# Sheet1.net
KiCad netlist of a schematic drawn in Altium Designer
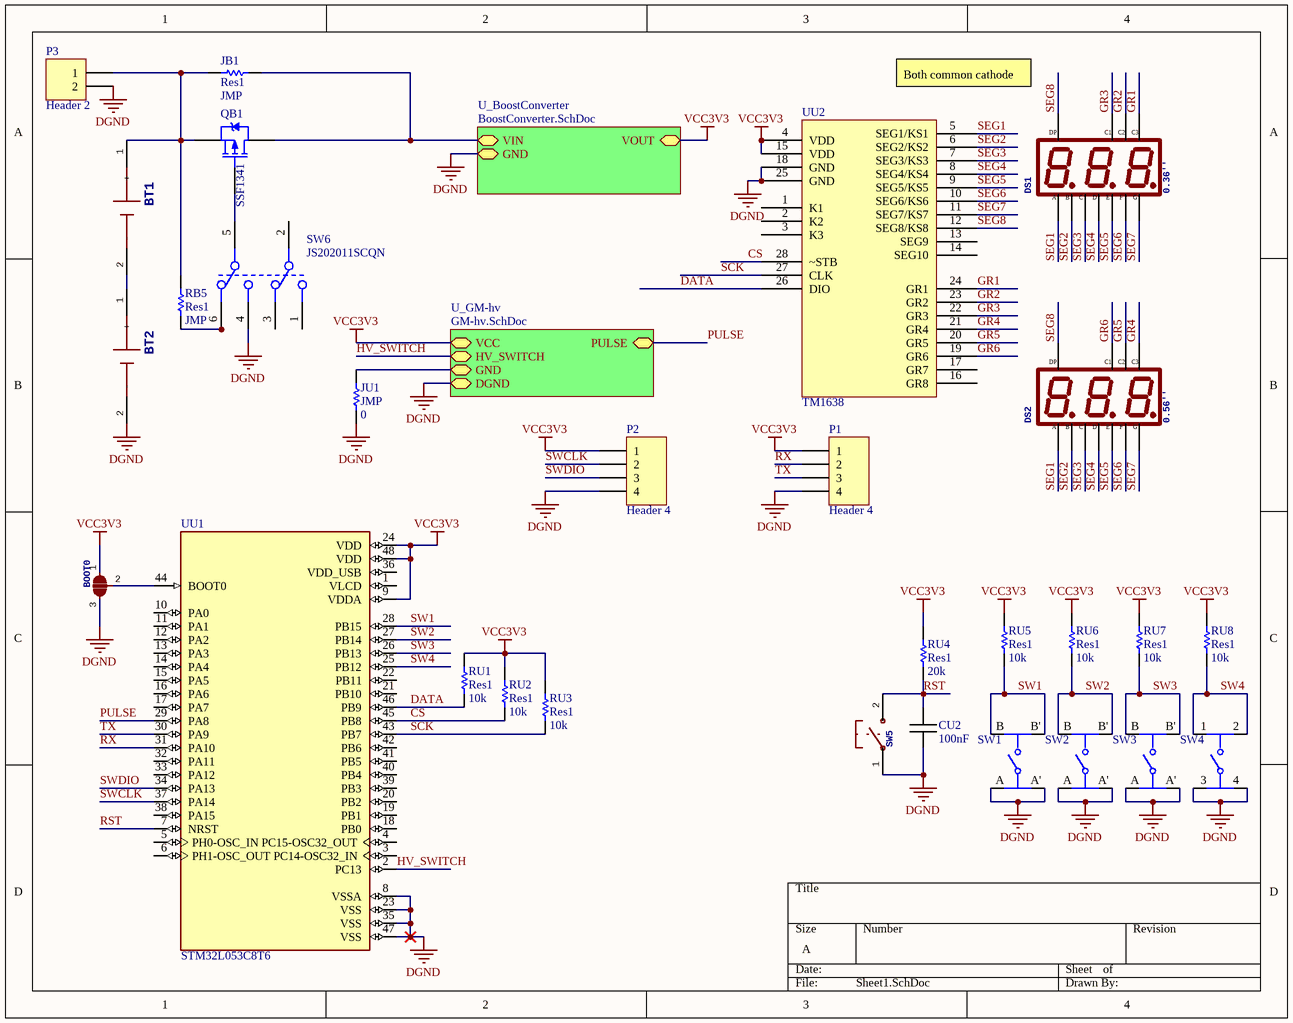
[diagram p0: Sheet1.SchDoc]

(export (version "E")
  (design (tool "Eeschema 10.0.6"))
  (components
    (comp (ref "BOOT0")
      (value "2-Way Solder Jumper")
      (footprint "SOLDERJUMPER_2WAY_OPEN_NOPASTE")
      (libsource (lib "Standard2") (part "SOLDERJUMPER_2WAY0603"))
    )
    (comp (ref "BT1")
      (value "Holder Cr2032 Gold Leads Smd")
      (footprint "AAA holder smd")
      (fields (field (name "MF") "MPD") (field (name "MP") "BU2032SM-BT-GTR"))
      (libsource (lib "Battery Holders") (part "BU2032SM-BT-GTR"))
    )
    (comp (ref "BT2")
      (value "Holder Cr2032 Gold Leads Smd")
      (footprint "AAA holder smd")
      (fields (field (name "MF") "MPD") (field (name "MP") "BU2032SM-BT-GTR"))
      (libsource (lib "Battery Holders") (part "BU2032SM-BT-GTR"))
    )
    (comp (ref "CU2") (value "100nF") (footprint "CAP0603R") (libsource (lib "Standard") (part "Capacitor")))
    (comp (ref "DS1")
      (value "0.36''")
      (footprint "7-seg 3bit 0.36")
      (fields (field (name "MP") "BA56-12EWA") (field (name "MF") "Kingbright"))
      (libsource (lib "LEDs") (part "BA56-12EWA"))
    )
    (comp (ref "DS2")
      (value "0.56''")
      (footprint "BA56-12EWA")
      (fields (field (name "MP") "BA56-12EWA") (field (name "MF") "Kingbright"))
      (libsource (lib "LEDs") (part "BA56-12EWA"))
    )
    (comp (ref "JB1")
      (value "Res1")
      (footprint "RES0603R")
      (description "Resistor")
      (fields (field (name "ALTIUM_VALUE") "JMP") (field (name "PUBLISHER") "Altium Limited"))
      (libsource (lib "Miscellaneous Devices") (part "Res1"))
    )
    (comp (ref "JU1")
      (value "JMP")
      (footprint "RES0603R")
      (description "Resistor")
      (fields (field (name "ALTIUM_VALUE") "0") (field (name "PUBLISHER") "Altium Limited"))
      (libsource (lib "Miscellaneous Devices") (part "Res1"))
    )
    (comp (ref "P1")
      (value "Header 4")
      (footprint "HDR1X4")
      (description "Header, 4-Pin")
      (fields (field (name "PUBLISHER") "Altium Limited"))
      (libsource (lib "Miscellaneous Connectors") (part "Header 4"))
    )
    (comp (ref "P2")
      (value "Header 4")
      (footprint "HDR1X4")
      (description "Header, 4-Pin")
      (fields (field (name "PUBLISHER") "Altium Limited"))
      (libsource (lib "Miscellaneous Connectors") (part "Header 4"))
    )
    (comp (ref "P3")
      (value "Header 2")
      (footprint "HDR1X2")
      (description "Header, 2-Pin")
      (fields (field (name "PUBLISHER") "Altium Limited"))
      (libsource (lib "Miscellaneous Connectors") (part "Header 2"))
    )
    (comp (ref "QB1")
      (value "SSF1341")
      (footprint "SOT23")
      (description "P-Channel Power MOSFET PMV65XP")
      (fields (field (name "PART NUMBER") "1758119"))
      (libsource (lib "Standard") (part "PMOS"))
    )
    (comp (ref "RB5")
      (value "Res1")
      (footprint "RES0603R")
      (description "Resistor")
      (fields (field (name "ALTIUM_VALUE") "JMP") (field (name "PUBLISHER") "Altium Limited"))
      (libsource (lib "Miscellaneous Devices") (part "Res1"))
    )
    (comp (ref "RU1")
      (value "Res1")
      (footprint "RES0603R")
      (description "Resistor")
      (fields (field (name "ALTIUM_VALUE") "10k") (field (name "PUBLISHER") "Altium Limited"))
      (libsource (lib "Miscellaneous Devices") (part "Res1"))
    )
    (comp (ref "RU2")
      (value "Res1")
      (footprint "RES0603R")
      (description "Resistor")
      (fields (field (name "ALTIUM_VALUE") "10k") (field (name "PUBLISHER") "Altium Limited"))
      (libsource (lib "Miscellaneous Devices") (part "Res1"))
    )
    (comp (ref "RU3")
      (value "Res1")
      (footprint "RES0603R")
      (description "Resistor")
      (fields (field (name "ALTIUM_VALUE") "10k") (field (name "PUBLISHER") "Altium Limited"))
      (libsource (lib "Miscellaneous Devices") (part "Res1"))
    )
    (comp (ref "RU4")
      (value "Res1")
      (footprint "RES0603R")
      (description "Resistor")
      (fields (field (name "ALTIUM_VALUE") "20k") (field (name "PUBLISHER") "Altium Limited"))
      (libsource (lib "Miscellaneous Devices") (part "Res1"))
    )
    (comp (ref "RU5")
      (value "Res1")
      (footprint "RES0603R")
      (description "Resistor")
      (fields (field (name "ALTIUM_VALUE") "10k") (field (name "PUBLISHER") "Altium Limited"))
      (libsource (lib "Standard") (part "Res1"))
    )
    (comp (ref "RU6")
      (value "Res1")
      (footprint "RES0603R")
      (description "Resistor")
      (fields (field (name "ALTIUM_VALUE") "10k") (field (name "PUBLISHER") "Altium Limited"))
      (libsource (lib "Standard") (part "Res1"))
    )
    (comp (ref "RU7")
      (value "Res1")
      (footprint "RES0603R")
      (description "Resistor")
      (fields (field (name "ALTIUM_VALUE") "10k") (field (name "PUBLISHER") "Altium Limited"))
      (libsource (lib "Standard") (part "Res1"))
    )
    (comp (ref "RU8")
      (value "Res1")
      (footprint "RES0603R")
      (description "Resistor")
      (fields (field (name "ALTIUM_VALUE") "10k") (field (name "PUBLISHER") "Altium Limited"))
      (libsource (lib "Standard") (part "Res1"))
    )
    (comp (ref "SW1")
      (value "EVQ-PAE05R")
      (footprint "FP-EVQ-PAE05R-MFG")
      (description "SWITCH TACTILE SPST-NO 0.02A 15V")
      (libsource (lib "Altium Content Vault") (part "75038bc65b1af1a6bd057da08483287"))
    )
    (comp (ref "SW2")
      (value "EVQ-PAE05R")
      (footprint "FP-EVQ-PAE05R-MFG")
      (description "SWITCH TACTILE SPST-NO 0.02A 15V")
      (libsource (lib "Altium Content Vault") (part "75038bc65b1af1a6bd057da08483287"))
    )
    (comp (ref "SW3")
      (value "EVQ-PAE05R")
      (footprint "FP-EVQ-PAE05R-MFG")
      (description "SWITCH TACTILE SPST-NO 0.02A 15V")
      (libsource (lib "Altium Content Vault") (part "75038bc65b1af1a6bd057da08483287"))
    )
    (comp (ref "SW4")
      (value "FSM100")
      (footprint "FP-FSM100-MFG")
      (description "SWITCH TACTILE SPST-NO 0.05A 24V")
      (libsource (lib "Altium Content Vault") (part "1adf0dd01260c80cf25a44bfd6b99ba"))
    )
    (comp (ref "SW5")
      (value "Switch")
      (footprint "PUSH_SMD_3x4")
      (fields (field (name "MANUFACTURER") "Omron") (field (name "MPN") "B3U-1000P"))
      (libsource (lib "Switches") (part "B3U-1000P"))
    )
    (comp (ref "SW6")
      (value "JS202011SCQN")
      (footprint "JS202011SCQN")
      (description "SWITCH SLIDE DPDT 300MA 6V")
      (libsource (lib "Switches") (part "JS202011SCQN"))
    )
    (comp (ref "UU1")
      (value "STM32L053C8T6")
      (footprint "LQFP48_7X7MM_0.5MMPP")
      (description "ARMÂ® CortexÂ®-M0+ STM32L0 Microcontroller IC 32-Bit 32MHz 64KB _64K x 8_ FLASH 48-LQFP _7x7_")
      (fields (field (name "DIGI-KEY_PART_NUMBER") "497-14906-ND") (field (name "MF") "STMicroelectronics"))
      (libsource (lib "STM") (part "STM32L053C8T6"))
    )
    (comp (ref "UU2")
      (value "TM1638")
      (footprint "SOP-28")
      (description "7Seg and keyboard driver")
      (libsource (lib "IC") (part "TM1638"))
    )
  )
  (nets
    (net (code "1") (name "/CS") (class "Default")
      (node (ref "RU2") (pin "2") (pinfunction "2_2") (pintype "passive"))
      (node (ref "UU1") (pin "45") (pinfunction "PB8_45") (pintype "bidirectional"))
      (node (ref "UU2") (pin "28") (pinfunction "~STB_28") (pintype "passive"))
    )
    (net (code "2") (name "/DATA") (class "Default")
      (node (ref "RU1") (pin "1") (pinfunction "1_1") (pintype "passive"))
      (node (ref "UU1") (pin "46") (pinfunction "PB9_46") (pintype "bidirectional"))
      (node (ref "UU2") (pin "26") (pinfunction "DIO_26") (pintype "passive"))
    )
    (net (code "3") (name "/GND") (class "Default")
      (node (ref "JU1") (pin "2") (pinfunction "2_2") (pintype "passive"))
    )
    (net (code "4") (name "/GR1") (class "Default")
      (node (ref "DS1") (pin "12") (pinfunction "CA@3_12") (pintype "passive"))
      (node (ref "UU2") (pin "24") (pinfunction "GR1_24") (pintype "passive"))
    )
    (net (code "5") (name "/GR2") (class "Default")
      (node (ref "DS1") (pin "9") (pinfunction "CA@2_9") (pintype "passive"))
      (node (ref "UU2") (pin "23") (pinfunction "GR2_23") (pintype "passive"))
    )
    (net (code "6") (name "/GR3") (class "Default")
      (node (ref "DS1") (pin "8") (pinfunction "CA@1_8") (pintype "passive"))
      (node (ref "UU2") (pin "22") (pinfunction "GR3_22") (pintype "passive"))
    )
    (net (code "7") (name "/GR4") (class "Default")
      (node (ref "DS2") (pin "12") (pinfunction "CA@3_12") (pintype "passive"))
      (node (ref "UU2") (pin "21") (pinfunction "GR4_21") (pintype "passive"))
    )
    (net (code "8") (name "/GR5") (class "Default")
      (node (ref "DS2") (pin "9") (pinfunction "CA@2_9") (pintype "passive"))
      (node (ref "UU2") (pin "20") (pinfunction "GR5_20") (pintype "passive"))
    )
    (net (code "9") (name "/GR6") (class "Default")
      (node (ref "DS2") (pin "8") (pinfunction "CA@1_8") (pintype "passive"))
      (node (ref "UU2") (pin "19") (pinfunction "GR6_19") (pintype "passive"))
    )
    (net (code "10") (name "/HV_SWITCH") (class "Default")
      (node (ref "UU1") (pin "2") (pinfunction "PC13_2") (pintype "bidirectional"))
    )
    (net (code "11") (name "/PULSE") (class "Default")
      (node (ref "UU1") (pin "29") (pinfunction "PA8_29") (pintype "bidirectional"))
    )
    (net (code "12") (name "/RST") (class "Default")
      (node (ref "CU2") (pin "1") (pinfunction "1_1") (pintype "passive"))
      (node (ref "RU4") (pin "2") (pinfunction "2_2") (pintype "passive"))
      (node (ref "SW5") (pin "2") (pinfunction "P$2_2") (pintype "passive"))
      (node (ref "UU1") (pin "7") (pinfunction "NRST_7") (pintype "bidirectional"))
    )
    (net (code "13") (name "/RX") (class "Default")
      (node (ref "P1") (pin "2") (pinfunction "2_2") (pintype "passive"))
      (node (ref "UU1") (pin "31") (pinfunction "PA10_31") (pintype "bidirectional"))
    )
    (net (code "14") (name "/SCK") (class "Default")
      (node (ref "RU3") (pin "2") (pinfunction "2_2") (pintype "passive"))
      (node (ref "UU1") (pin "43") (pinfunction "PB7_43") (pintype "bidirectional"))
      (node (ref "UU2") (pin "27") (pinfunction "CLK_27") (pintype "passive"))
    )
    (net (code "15") (name "/SEG1") (class "Default")
      (node (ref "DS1") (pin "11") (pinfunction "A_11") (pintype "passive"))
      (node (ref "DS2") (pin "11") (pinfunction "A_11") (pintype "passive"))
      (node (ref "UU2") (pin "5") (pinfunction "SEG1/KS1_5") (pintype "passive"))
    )
    (net (code "16") (name "/SEG2") (class "Default")
      (node (ref "DS1") (pin "7") (pinfunction "B_7") (pintype "passive"))
      (node (ref "DS2") (pin "7") (pinfunction "B_7") (pintype "passive"))
      (node (ref "UU2") (pin "6") (pinfunction "SEG2/KS2_6") (pintype "passive"))
    )
    (net (code "17") (name "/SEG3") (class "Default")
      (node (ref "DS1") (pin "4") (pinfunction "C_4") (pintype "passive"))
      (node (ref "DS2") (pin "4") (pinfunction "C_4") (pintype "passive"))
      (node (ref "UU2") (pin "7") (pinfunction "SEG3/KS3_7") (pintype "passive"))
    )
    (net (code "18") (name "/SEG4") (class "Default")
      (node (ref "DS1") (pin "2") (pinfunction "D_2") (pintype "passive"))
      (node (ref "DS2") (pin "2") (pinfunction "D_2") (pintype "passive"))
      (node (ref "UU2") (pin "8") (pinfunction "SEG4/KS4_8") (pintype "passive"))
    )
    (net (code "19") (name "/SEG5") (class "Default")
      (node (ref "DS1") (pin "1") (pinfunction "E_1") (pintype "passive"))
      (node (ref "DS2") (pin "1") (pinfunction "E_1") (pintype "passive"))
      (node (ref "UU2") (pin "9") (pinfunction "SEG5/KS5_9") (pintype "passive"))
    )
    (net (code "20") (name "/SEG6") (class "Default")
      (node (ref "DS1") (pin "10") (pinfunction "F_10") (pintype "passive"))
      (node (ref "DS2") (pin "10") (pinfunction "F_10") (pintype "passive"))
      (node (ref "UU2") (pin "10") (pinfunction "SEG6/KS6_10") (pintype "passive"))
    )
    (net (code "21") (name "/SEG7") (class "Default")
      (node (ref "DS1") (pin "5") (pinfunction "G_5") (pintype "passive"))
      (node (ref "DS2") (pin "5") (pinfunction "G_5") (pintype "passive"))
      (node (ref "UU2") (pin "11") (pinfunction "SEG7/KS7_11") (pintype "passive"))
    )
    (net (code "22") (name "/SEG8") (class "Default")
      (node (ref "DS1") (pin "3") (pinfunction "DP_3") (pintype "passive"))
      (node (ref "DS2") (pin "3") (pinfunction "DP_3") (pintype "passive"))
      (node (ref "UU2") (pin "12") (pinfunction "SEG8/KS8_12") (pintype "passive"))
    )
    (net (code "23") (name "/SW1") (class "Default")
      (node (ref "RU5") (pin "1") (pinfunction "1_1") (pintype "passive"))
      (node (ref "SW1") (pin "B") (pinfunction "B_B") (pintype "passive"))
      (node (ref "SW1") (pin "B'") (pinfunction "B'_B'") (pintype "passive"))
      (node (ref "UU1") (pin "28") (pinfunction "PB15_28") (pintype "bidirectional"))
    )
    (net (code "24") (name "/SW2") (class "Default")
      (node (ref "RU6") (pin "1") (pinfunction "1_1") (pintype "passive"))
      (node (ref "SW2") (pin "B") (pinfunction "B_B") (pintype "passive"))
      (node (ref "SW2") (pin "B'") (pinfunction "B'_B'") (pintype "passive"))
      (node (ref "UU1") (pin "27") (pinfunction "PB14_27") (pintype "bidirectional"))
    )
    (net (code "25") (name "/SW3") (class "Default")
      (node (ref "RU7") (pin "1") (pinfunction "1_1") (pintype "passive"))
      (node (ref "SW3") (pin "B") (pinfunction "B_B") (pintype "passive"))
      (node (ref "SW3") (pin "B'") (pinfunction "B'_B'") (pintype "passive"))
      (node (ref "UU1") (pin "26") (pinfunction "PB13_26") (pintype "bidirectional"))
    )
    (net (code "26") (name "/SW4") (class "Default")
      (node (ref "RU8") (pin "1") (pinfunction "1_1") (pintype "passive"))
      (node (ref "SW4") (pin "1") (pinfunction "1_1") (pintype "passive"))
      (node (ref "SW4") (pin "2") (pinfunction "2_2") (pintype "passive"))
      (node (ref "UU1") (pin "25") (pinfunction "PB12_25") (pintype "bidirectional"))
    )
    (net (code "27") (name "/SWCLK") (class "Default")
      (node (ref "P2") (pin "2") (pinfunction "2_2") (pintype "passive"))
      (node (ref "UU1") (pin "37") (pinfunction "PA14_37") (pintype "bidirectional"))
    )
    (net (code "28") (name "/SWDIO") (class "Default")
      (node (ref "P2") (pin "3") (pinfunction "3_3") (pintype "passive"))
      (node (ref "UU1") (pin "34") (pinfunction "PA13_34") (pintype "bidirectional"))
    )
    (net (code "29") (name "/TX") (class "Default")
      (node (ref "P1") (pin "3") (pinfunction "3_3") (pintype "passive"))
      (node (ref "UU1") (pin "30") (pinfunction "PA9_30") (pintype "bidirectional"))
    )
    (net (code "30") (name "/VIN") (class "Default")
      (node (ref "JB1") (pin "1") (pinfunction "1_1") (pintype "passive"))
      (node (ref "QB1") (pin "3") (pinfunction "D_3") (pintype "passive"))
    )
    (net (code "31") (name "DGND") (class "Default")
      (node (ref "BOOT0") (pin "3") (pinfunction "3_3") (pintype "passive"))
      (node (ref "BT2") (pin "2") (pinfunction "-_2") (pintype "passive"))
      (node (ref "CU2") (pin "2") (pinfunction "1_2") (pintype "passive"))
      (node (ref "JU1") (pin "1") (pinfunction "1_1") (pintype "passive"))
      (node (ref "P1") (pin "4") (pinfunction "4_4") (pintype "passive"))
      (node (ref "P2") (pin "4") (pinfunction "4_4") (pintype "passive"))
      (node (ref "P3") (pin "2") (pinfunction "2_2") (pintype "passive"))
      (node (ref "SW1") (pin "A") (pinfunction "A_A") (pintype "passive"))
      (node (ref "SW1") (pin "A'") (pinfunction "A'_A'") (pintype "passive"))
      (node (ref "SW2") (pin "A") (pinfunction "A_A") (pintype "passive"))
      (node (ref "SW2") (pin "A'") (pinfunction "A'_A'") (pintype "passive"))
      (node (ref "SW3") (pin "A") (pinfunction "A_A") (pintype "passive"))
      (node (ref "SW3") (pin "A'") (pinfunction "A'_A'") (pintype "passive"))
      (node (ref "SW4") (pin "3") (pinfunction "3_3") (pintype "passive"))
      (node (ref "SW4") (pin "4") (pinfunction "4_4") (pintype "passive"))
      (node (ref "SW5") (pin "1") (pinfunction "P$1_1") (pintype "passive"))
      (node (ref "SW6") (pin "4") (pinfunction "4_4") (pintype "passive"))
      (node (ref "UU1") (pin "23") (pinfunction "VSS_23") (pintype "bidirectional"))
      (node (ref "UU1") (pin "35") (pinfunction "VSS_35") (pintype "bidirectional"))
      (node (ref "UU1") (pin "47") (pinfunction "VSS_47") (pintype "bidirectional"))
      (node (ref "UU1") (pin "8") (pinfunction "VSSA_8") (pintype "bidirectional"))
      (node (ref "UU2") (pin "18") (pinfunction "GND_18") (pintype "passive"))
      (node (ref "UU2") (pin "25") (pinfunction "GND_25") (pintype "passive"))
    )
    (net (code "32") (name "Net-(BT1-+)") (class "Default")
      (node (ref "BT1") (pin "1") (pinfunction "+_1") (pintype "passive"))
      (node (ref "JB1") (pin "2") (pinfunction "2_2") (pintype "passive"))
      (node (ref "P3") (pin "1") (pinfunction "1_1") (pintype "passive"))
      (node (ref "QB1") (pin "2") (pinfunction "S_2") (pintype "passive"))
      (node (ref "RB5") (pin "1") (pinfunction "1_1") (pintype "passive"))
    )
    (net (code "33") (name "Net-(BT1--)") (class "Default")
      (node (ref "BT1") (pin "2") (pinfunction "-_2") (pintype "passive"))
      (node (ref "BT2") (pin "1") (pinfunction "+_1") (pintype "passive"))
    )
    (net (code "34") (name "Net-(QB1-G)") (class "Default")
      (node (ref "QB1") (pin "1") (pinfunction "G_1") (pintype "passive"))
      (node (ref "SW6") (pin "5") (pinfunction "5_5") (pintype "passive"))
    )
    (net (code "35") (name "Net-(RB5-Pad2)") (class "Default")
      (node (ref "RB5") (pin "2") (pinfunction "2_2") (pintype "passive"))
      (node (ref "SW6") (pin "6") (pinfunction "6_6") (pintype "passive"))
    )
    (net (code "36") (name "Net-(UU1-BOOT0)") (class "Default")
      (node (ref "BOOT0") (pin "2") (pinfunction "2_2") (pintype "passive"))
      (node (ref "UU1") (pin "44") (pinfunction "BOOT0_44") (pintype "input"))
    )
    (net (code "37") (name "VCC3V3") (class "Default")
      (node (ref "BOOT0") (pin "1") (pinfunction "1_1") (pintype "passive"))
      (node (ref "P1") (pin "1") (pinfunction "1_1") (pintype "passive"))
      (node (ref "P2") (pin "1") (pinfunction "1_1") (pintype "passive"))
      (node (ref "RU1") (pin "2") (pinfunction "2_2") (pintype "passive"))
      (node (ref "RU2") (pin "1") (pinfunction "1_1") (pintype "passive"))
      (node (ref "RU3") (pin "1") (pinfunction "1_1") (pintype "passive"))
      (node (ref "RU4") (pin "1") (pinfunction "1_1") (pintype "passive"))
      (node (ref "RU5") (pin "2") (pinfunction "2_2") (pintype "passive"))
      (node (ref "RU6") (pin "2") (pinfunction "2_2") (pintype "passive"))
      (node (ref "RU7") (pin "2") (pinfunction "2_2") (pintype "passive"))
      (node (ref "RU8") (pin "2") (pinfunction "2_2") (pintype "passive"))
      (node (ref "UU1") (pin "24") (pinfunction "VDD_24") (pintype "bidirectional"))
      (node (ref "UU1") (pin "48") (pinfunction "VDD_48") (pintype "bidirectional"))
      (node (ref "UU1") (pin "9") (pinfunction "VDDA_9") (pintype "bidirectional"))
      (node (ref "UU2") (pin "15") (pinfunction "VDD_15") (pintype "passive"))
      (node (ref "UU2") (pin "4") (pinfunction "VDD_4") (pintype "passive"))
    )
    (net (code "38") (name "unconnected-(SW6-Pad1)") (class "Default")
      (node (ref "SW6") (pin "1") (pinfunction "1_1") (pintype "passive"))
    )
    (net (code "39") (name "unconnected-(SW6-Pad2)") (class "Default")
      (node (ref "SW6") (pin "2") (pinfunction "2_2") (pintype "passive"))
    )
    (net (code "40") (name "unconnected-(SW6-Pad3)") (class "Default")
      (node (ref "SW6") (pin "3") (pinfunction "3_3") (pintype "passive"))
    )
    (net (code "41") (name "unconnected-(UU1-PA0-Pad10)") (class "Default")
      (node (ref "UU1") (pin "10") (pinfunction "PA0_10") (pintype "bidirectional"))
    )
    (net (code "42") (name "unconnected-(UU1-PA1-Pad11)") (class "Default")
      (node (ref "UU1") (pin "11") (pinfunction "PA1_11") (pintype "bidirectional"))
    )
    (net (code "43") (name "unconnected-(UU1-PA2-Pad12)") (class "Default")
      (node (ref "UU1") (pin "12") (pinfunction "PA2_12") (pintype "bidirectional"))
    )
    (net (code "44") (name "unconnected-(UU1-PA3-Pad13)") (class "Default")
      (node (ref "UU1") (pin "13") (pinfunction "PA3_13") (pintype "bidirectional"))
    )
    (net (code "45") (name "unconnected-(UU1-PA4-Pad14)") (class "Default")
      (node (ref "UU1") (pin "14") (pinfunction "PA4_14") (pintype "bidirectional"))
    )
    (net (code "46") (name "unconnected-(UU1-PA5-Pad15)") (class "Default")
      (node (ref "UU1") (pin "15") (pinfunction "PA5_15") (pintype "bidirectional"))
    )
    (net (code "47") (name "unconnected-(UU1-PA6-Pad16)") (class "Default")
      (node (ref "UU1") (pin "16") (pinfunction "PA6_16") (pintype "bidirectional"))
    )
    (net (code "48") (name "unconnected-(UU1-PA7-Pad17)") (class "Default")
      (node (ref "UU1") (pin "17") (pinfunction "PA7_17") (pintype "bidirectional"))
    )
    (net (code "49") (name "unconnected-(UU1-PA11-Pad32)") (class "Default")
      (node (ref "UU1") (pin "32") (pinfunction "PA11_32") (pintype "bidirectional"))
    )
    (net (code "50") (name "unconnected-(UU1-PA12-Pad33)") (class "Default")
      (node (ref "UU1") (pin "33") (pinfunction "PA12_33") (pintype "bidirectional"))
    )
    (net (code "51") (name "unconnected-(UU1-PA15-Pad38)") (class "Default")
      (node (ref "UU1") (pin "38") (pinfunction "PA15_38") (pintype "bidirectional"))
    )
    (net (code "52") (name "unconnected-(UU1-PB0-Pad18)") (class "Default")
      (node (ref "UU1") (pin "18") (pinfunction "PB0_18") (pintype "bidirectional"))
    )
    (net (code "53") (name "unconnected-(UU1-PB1-Pad19)") (class "Default")
      (node (ref "UU1") (pin "19") (pinfunction "PB1_19") (pintype "bidirectional"))
    )
    (net (code "54") (name "unconnected-(UU1-PB2-Pad20)") (class "Default")
      (node (ref "UU1") (pin "20") (pinfunction "PB2_20") (pintype "bidirectional"))
    )
    (net (code "55") (name "unconnected-(UU1-PB3-Pad39)") (class "Default")
      (node (ref "UU1") (pin "39") (pinfunction "PB3_39") (pintype "bidirectional"))
    )
    (net (code "56") (name "unconnected-(UU1-PB4-Pad40)") (class "Default")
      (node (ref "UU1") (pin "40") (pinfunction "PB4_40") (pintype "bidirectional"))
    )
    (net (code "57") (name "unconnected-(UU1-PB5-Pad41)") (class "Default")
      (node (ref "UU1") (pin "41") (pinfunction "PB5_41") (pintype "bidirectional"))
    )
    (net (code "58") (name "unconnected-(UU1-PB6-Pad42)") (class "Default")
      (node (ref "UU1") (pin "42") (pinfunction "PB6_42") (pintype "bidirectional"))
    )
    (net (code "59") (name "unconnected-(UU1-PB10-Pad21)") (class "Default")
      (node (ref "UU1") (pin "21") (pinfunction "PB10_21") (pintype "bidirectional"))
    )
    (net (code "60") (name "unconnected-(UU1-PB11-Pad22)") (class "Default")
      (node (ref "UU1") (pin "22") (pinfunction "PB11_22") (pintype "bidirectional"))
    )
    (net (code "61") (name "unconnected-(UU1-PC14-OSC32_IN-Pad3)") (class "Default")
      (node (ref "UU1") (pin "3") (pinfunction "PC14-OSC32_IN_3") (pintype "bidirectional"))
    )
    (net (code "62") (name "unconnected-(UU1-PC15-OSC32_OUT-Pad4)") (class "Default")
      (node (ref "UU1") (pin "4") (pinfunction "PC15-OSC32_OUT_4") (pintype "bidirectional"))
    )
    (net (code "63") (name "unconnected-(UU1-PH0-OSC_IN-Pad5)") (class "Default")
      (node (ref "UU1") (pin "5") (pinfunction "PH0-OSC_IN_5") (pintype "bidirectional"))
    )
    (net (code "64") (name "unconnected-(UU1-PH1-OSC_OUT-Pad6)") (class "Default")
      (node (ref "UU1") (pin "6") (pinfunction "PH1-OSC_OUT_6") (pintype "bidirectional"))
    )
    (net (code "65") (name "unconnected-(UU1-VDD_USB-Pad36)") (class "Default")
      (node (ref "UU1") (pin "36") (pinfunction "VDD_USB_36") (pintype "bidirectional"))
    )
    (net (code "66") (name "unconnected-(UU1-VLCD-Pad1)") (class "Default")
      (node (ref "UU1") (pin "1") (pinfunction "VLCD_1") (pintype "bidirectional"))
    )
    (net (code "67") (name "unconnected-(UU2-GR7-Pad17)") (class "Default")
      (node (ref "UU2") (pin "17") (pinfunction "GR7_17") (pintype "passive"))
    )
    (net (code "68") (name "unconnected-(UU2-GR8-Pad16)") (class "Default")
      (node (ref "UU2") (pin "16") (pinfunction "GR8_16") (pintype "passive"))
    )
    (net (code "69") (name "unconnected-(UU2-K1-Pad1)") (class "Default")
      (node (ref "UU2") (pin "1") (pinfunction "K1_1") (pintype "passive"))
    )
    (net (code "70") (name "unconnected-(UU2-K2-Pad2)") (class "Default")
      (node (ref "UU2") (pin "2") (pinfunction "K2_2") (pintype "passive"))
    )
    (net (code "71") (name "unconnected-(UU2-K3-Pad3)") (class "Default")
      (node (ref "UU2") (pin "3") (pinfunction "K3_3") (pintype "passive"))
    )
    (net (code "72") (name "unconnected-(UU2-SEG9-Pad13)") (class "Default")
      (node (ref "UU2") (pin "13") (pinfunction "SEG9_13") (pintype "passive"))
    )
    (net (code "73") (name "unconnected-(UU2-SEG10-Pad14)") (class "Default")
      (node (ref "UU2") (pin "14") (pinfunction "SEG10_14") (pintype "passive"))
    )
  )
)
